# L298.net
KiCad netlist of a schematic drawn in EAGLE
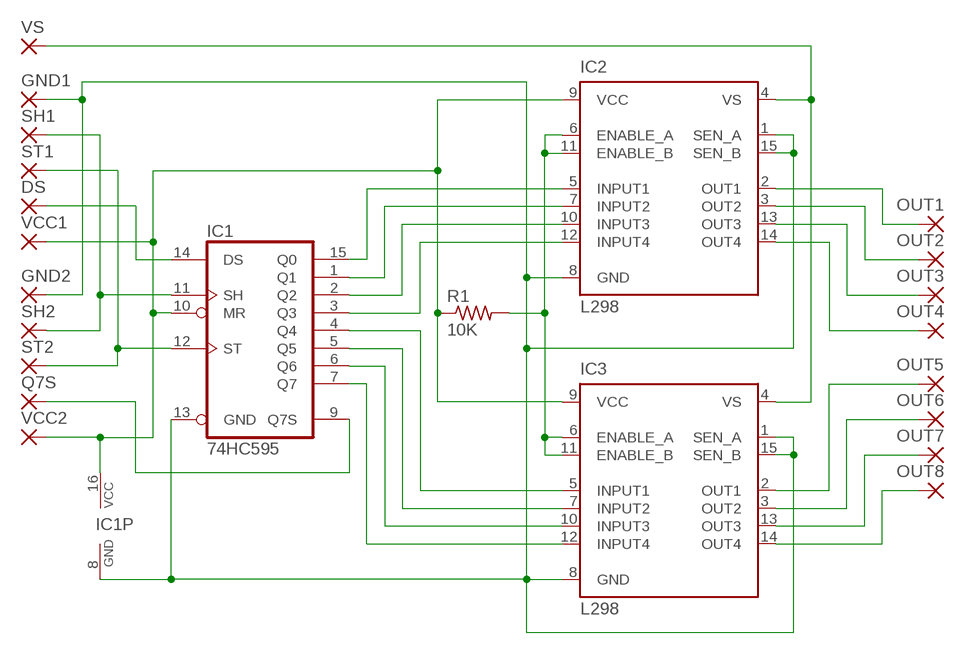
[diagram p0: schematic, sheet 1]

(export (version "E")
  (design (tool "Eeschema 10.0.6"))
  (components
    (comp (ref "DS")
      (value "1,6/0,8")
      (footprint "eagle-import:1,6_0,8")
      (libsource (lib "eagle-import") (part "1,6/0,8"))
    )
    (comp (ref "GND1")
      (value "1,6/0,8")
      (footprint "eagle-import:1,6_0,8")
      (libsource (lib "eagle-import") (part "1,6/0,8"))
    )
    (comp (ref "GND2")
      (value "1,6/0,8")
      (footprint "eagle-import:1,6_0,8")
      (libsource (lib "eagle-import") (part "1,6/0,8"))
    )
    (comp (ref "IC1")
      (value "74HC595")
      (footprint "eagle-import:DIL16")
      (libsource (lib "eagle-import") (part "74595NHC"))
    )
    (comp (ref "IC2")
      (value "L298")
      (footprint "eagle-import:MULTIWATT-15")
      (fields (field (name "MPN") "L298N"))
      (libsource (lib "eagle-import") (part "L298"))
    )
    (comp (ref "IC3")
      (value "L298")
      (footprint "eagle-import:MULTIWATT-15")
      (fields (field (name "MPN") "L298N"))
      (libsource (lib "eagle-import") (part "L298"))
    )
    (comp (ref "OUT1")
      (value "1,6/0,8")
      (footprint "eagle-import:1,6_0,8")
      (libsource (lib "eagle-import") (part "1,6/0,8"))
    )
    (comp (ref "OUT2")
      (value "1,6/0,8")
      (footprint "eagle-import:1,6_0,8")
      (libsource (lib "eagle-import") (part "1,6/0,8"))
    )
    (comp (ref "OUT3")
      (value "1,6/0,8")
      (footprint "eagle-import:1,6_0,8")
      (libsource (lib "eagle-import") (part "1,6/0,8"))
    )
    (comp (ref "OUT4")
      (value "1,6/0,8")
      (footprint "eagle-import:1,6_0,8")
      (libsource (lib "eagle-import") (part "1,6/0,8"))
    )
    (comp (ref "OUT5")
      (value "1,6/0,8")
      (footprint "eagle-import:1,6_0,8")
      (libsource (lib "eagle-import") (part "1,6/0,8"))
    )
    (comp (ref "OUT6")
      (value "1,6/0,8")
      (footprint "eagle-import:1,6_0,8")
      (libsource (lib "eagle-import") (part "1,6/0,8"))
    )
    (comp (ref "OUT7")
      (value "1,6/0,8")
      (footprint "eagle-import:1,6_0,8")
      (libsource (lib "eagle-import") (part "1,6/0,8"))
    )
    (comp (ref "OUT8")
      (value "1,6/0,8")
      (footprint "eagle-import:1,6_0,8")
      (libsource (lib "eagle-import") (part "1,6/0,8"))
    )
    (comp (ref "Q7S")
      (value "1,6/0,8")
      (footprint "eagle-import:1,6_0,8")
      (libsource (lib "eagle-import") (part "1,6/0,8"))
    )
    (comp (ref "R1")
      (value "10K")
      (footprint "eagle-import:0411_12")
      (libsource (lib "eagle-import") (part "R-US_0411/12"))
    )
    (comp (ref "SH1")
      (value "1,6/0,8")
      (footprint "eagle-import:1,6_0,8")
      (libsource (lib "eagle-import") (part "1,6/0,8"))
    )
    (comp (ref "SH2")
      (value "1,6/0,8")
      (footprint "eagle-import:1,6_0,8")
      (libsource (lib "eagle-import") (part "1,6/0,8"))
    )
    (comp (ref "ST1")
      (value "1,6/0,8")
      (footprint "eagle-import:1,6_0,8")
      (libsource (lib "eagle-import") (part "1,6/0,8"))
    )
    (comp (ref "ST2")
      (value "1,6/0,8")
      (footprint "eagle-import:1,6_0,8")
      (libsource (lib "eagle-import") (part "1,6/0,8"))
    )
    (comp (ref "VCC1")
      (value "1,6/0,8")
      (footprint "eagle-import:1,6_0,8")
      (libsource (lib "eagle-import") (part "1,6/0,8"))
    )
    (comp (ref "VCC2")
      (value "1,6/0,8")
      (footprint "eagle-import:1,6_0,8")
      (libsource (lib "eagle-import") (part "1,6/0,8"))
    )
    (comp (ref "VS")
      (value "1,6/0,8")
      (footprint "eagle-import:1,6_0,8")
      (libsource (lib "eagle-import") (part "1,6/0,8"))
    )
  )
  (nets
    (net (code "1") (name "Net-(DS-P)") (class "Default")
      (node (ref "DS") (pin "1") (pinfunction "P_1") (pintype "passive"))
      (node (ref "IC1") (pin "14") (pinfunction "DS_14") (pintype "input"))
    )
    (net (code "2") (name "Net-(GND1-P)") (class "Default")
      (node (ref "GND1") (pin "1") (pinfunction "P_1") (pintype "passive"))
      (node (ref "GND2") (pin "1") (pinfunction "P_1") (pintype "passive"))
      (node (ref "IC1") (pin "13") (pinfunction "GND_13") (pintype "input"))
      (node (ref "IC1") (pin "8") (pinfunction "GND_8") (pintype "power_in"))
      (node (ref "IC2") (pin "1") (pinfunction "SEN_A_1") (pintype "input"))
      (node (ref "IC2") (pin "15") (pinfunction "SEN_B_15") (pintype "input"))
      (node (ref "IC2") (pin "8") (pinfunction "GND_8") (pintype "power_in"))
      (node (ref "IC3") (pin "1") (pinfunction "SEN_A_1") (pintype "input"))
      (node (ref "IC3") (pin "15") (pinfunction "SEN_B_15") (pintype "input"))
      (node (ref "IC3") (pin "8") (pinfunction "GND_8") (pintype "power_in"))
    )
    (net (code "3") (name "Net-(IC1A-MR)") (class "Default")
      (node (ref "IC1") (pin "10") (pinfunction "MR_10") (pintype "input"))
      (node (ref "IC1") (pin "16") (pinfunction "VCC_16") (pintype "power_in"))
      (node (ref "IC2") (pin "9") (pinfunction "VCC_9") (pintype "power_in"))
      (node (ref "IC3") (pin "9") (pinfunction "VCC_9") (pintype "power_in"))
      (node (ref "R1") (pin "1") (pinfunction "1_1") (pintype "passive"))
      (node (ref "VCC1") (pin "1") (pinfunction "P_1") (pintype "passive"))
      (node (ref "VCC2") (pin "1") (pinfunction "P_1") (pintype "passive"))
    )
    (net (code "4") (name "Net-(IC1A-Q0)") (class "Default")
      (node (ref "IC1") (pin "15") (pinfunction "Q0_15") (pintype "tri_state"))
      (node (ref "IC2") (pin "5") (pinfunction "INPUT1_5") (pintype "input"))
    )
    (net (code "5") (name "Net-(IC1A-Q1)") (class "Default")
      (node (ref "IC1") (pin "1") (pinfunction "Q1_1") (pintype "tri_state"))
      (node (ref "IC2") (pin "7") (pinfunction "INPUT2_7") (pintype "input"))
    )
    (net (code "6") (name "Net-(IC1A-Q2)") (class "Default")
      (node (ref "IC1") (pin "2") (pinfunction "Q2_2") (pintype "tri_state"))
      (node (ref "IC2") (pin "10") (pinfunction "INPUT3_10") (pintype "input"))
    )
    (net (code "7") (name "Net-(IC1A-Q3)") (class "Default")
      (node (ref "IC1") (pin "3") (pinfunction "Q3_3") (pintype "tri_state"))
      (node (ref "IC2") (pin "12") (pinfunction "INPUT4_12") (pintype "input"))
    )
    (net (code "8") (name "Net-(IC1A-Q4)") (class "Default")
      (node (ref "IC1") (pin "4") (pinfunction "Q4_4") (pintype "tri_state"))
      (node (ref "IC3") (pin "5") (pinfunction "INPUT1_5") (pintype "input"))
    )
    (net (code "9") (name "Net-(IC1A-Q5)") (class "Default")
      (node (ref "IC1") (pin "5") (pinfunction "Q5_5") (pintype "tri_state"))
      (node (ref "IC3") (pin "7") (pinfunction "INPUT2_7") (pintype "input"))
    )
    (net (code "10") (name "Net-(IC1A-Q6)") (class "Default")
      (node (ref "IC1") (pin "6") (pinfunction "Q6_6") (pintype "tri_state"))
      (node (ref "IC3") (pin "10") (pinfunction "INPUT3_10") (pintype "input"))
    )
    (net (code "11") (name "Net-(IC1A-Q7)") (class "Default")
      (node (ref "IC1") (pin "7") (pinfunction "Q7_7") (pintype "tri_state"))
      (node (ref "IC3") (pin "12") (pinfunction "INPUT4_12") (pintype "input"))
    )
    (net (code "12") (name "Net-(IC1A-Q7S)") (class "Default")
      (node (ref "IC1") (pin "9") (pinfunction "Q7S_9") (pintype "tri_state"))
      (node (ref "Q7S") (pin "1") (pinfunction "P_1") (pintype "passive"))
    )
    (net (code "13") (name "Net-(IC1A-SH)") (class "Default")
      (node (ref "IC1") (pin "11") (pinfunction "SH_11") (pintype "input"))
      (node (ref "SH1") (pin "1") (pinfunction "P_1") (pintype "passive"))
      (node (ref "SH2") (pin "1") (pinfunction "P_1") (pintype "passive"))
    )
    (net (code "14") (name "Net-(IC1A-ST)") (class "Default")
      (node (ref "IC1") (pin "12") (pinfunction "ST_12") (pintype "input"))
      (node (ref "ST1") (pin "1") (pinfunction "P_1") (pintype "passive"))
      (node (ref "ST2") (pin "1") (pinfunction "P_1") (pintype "passive"))
    )
    (net (code "15") (name "Net-(IC2-ENABLE_A)") (class "Default")
      (node (ref "IC2") (pin "11") (pinfunction "ENABLE_B_11") (pintype "input"))
      (node (ref "IC2") (pin "6") (pinfunction "ENABLE_A_6") (pintype "input"))
      (node (ref "IC3") (pin "11") (pinfunction "ENABLE_B_11") (pintype "input"))
      (node (ref "IC3") (pin "6") (pinfunction "ENABLE_A_6") (pintype "input"))
      (node (ref "R1") (pin "2") (pinfunction "2_2") (pintype "passive"))
    )
    (net (code "16") (name "Net-(IC2-OUT1)") (class "Default")
      (node (ref "IC2") (pin "2") (pinfunction "OUT1_2") (pintype "output"))
      (node (ref "OUT1") (pin "1") (pinfunction "P_1") (pintype "passive"))
    )
    (net (code "17") (name "Net-(IC2-OUT2)") (class "Default")
      (node (ref "IC2") (pin "3") (pinfunction "OUT2_3") (pintype "output"))
      (node (ref "OUT2") (pin "1") (pinfunction "P_1") (pintype "passive"))
    )
    (net (code "18") (name "Net-(IC2-OUT3)") (class "Default")
      (node (ref "IC2") (pin "13") (pinfunction "OUT3_13") (pintype "output"))
      (node (ref "OUT3") (pin "1") (pinfunction "P_1") (pintype "passive"))
    )
    (net (code "19") (name "Net-(IC2-OUT4)") (class "Default")
      (node (ref "IC2") (pin "14") (pinfunction "OUT4_14") (pintype "output"))
      (node (ref "OUT4") (pin "1") (pinfunction "P_1") (pintype "passive"))
    )
    (net (code "20") (name "Net-(IC2-VS)") (class "Default")
      (node (ref "IC2") (pin "4") (pinfunction "VS_4") (pintype "power_in"))
      (node (ref "IC3") (pin "4") (pinfunction "VS_4") (pintype "power_in"))
      (node (ref "VS") (pin "1") (pinfunction "P_1") (pintype "passive"))
    )
    (net (code "21") (name "Net-(IC3-OUT1)") (class "Default")
      (node (ref "IC3") (pin "2") (pinfunction "OUT1_2") (pintype "output"))
      (node (ref "OUT5") (pin "1") (pinfunction "P_1") (pintype "passive"))
    )
    (net (code "22") (name "Net-(IC3-OUT2)") (class "Default")
      (node (ref "IC3") (pin "3") (pinfunction "OUT2_3") (pintype "output"))
      (node (ref "OUT6") (pin "1") (pinfunction "P_1") (pintype "passive"))
    )
    (net (code "23") (name "Net-(IC3-OUT3)") (class "Default")
      (node (ref "IC3") (pin "13") (pinfunction "OUT3_13") (pintype "output"))
      (node (ref "OUT7") (pin "1") (pinfunction "P_1") (pintype "passive"))
    )
    (net (code "24") (name "Net-(IC3-OUT4)") (class "Default")
      (node (ref "IC3") (pin "14") (pinfunction "OUT4_14") (pintype "output"))
      (node (ref "OUT8") (pin "1") (pinfunction "P_1") (pintype "passive"))
    )
  )
)
